# exp_4.net
KiCad netlist of a schematic drawn in EAGLE
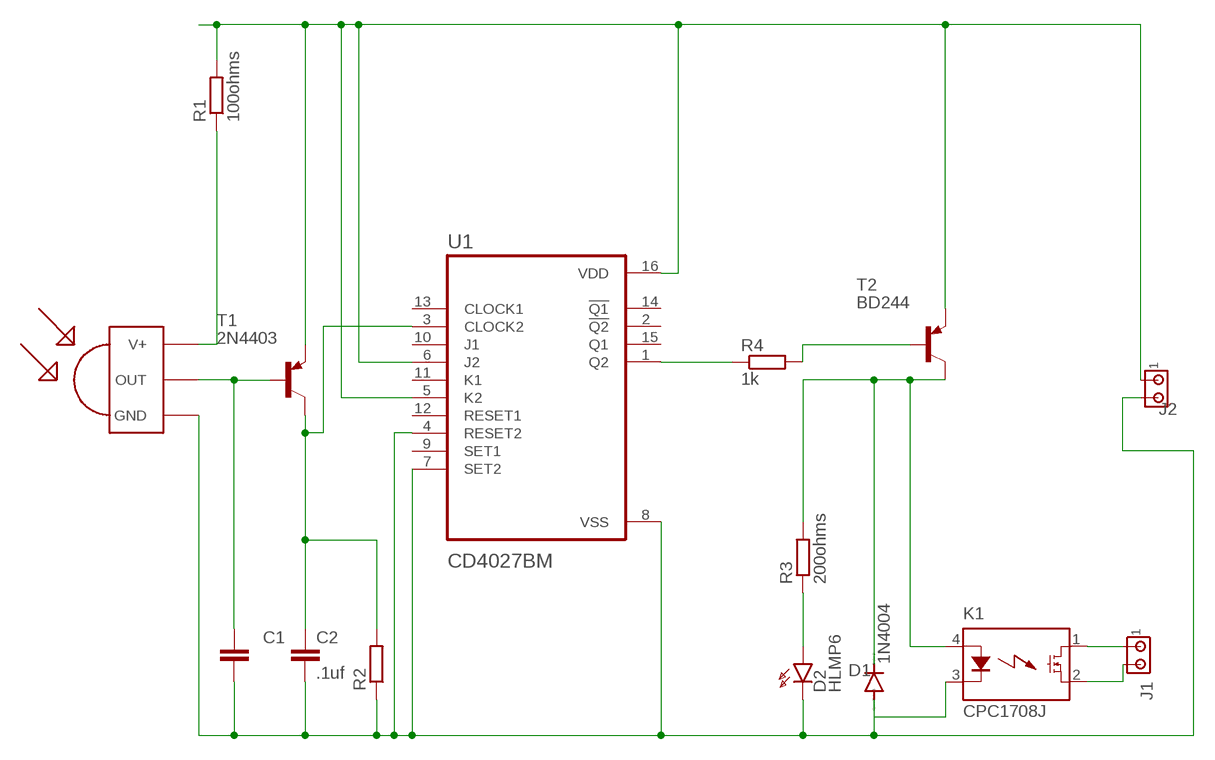
[diagram p0: schematic, sheet 1]

(export (version "E")
  (design (tool "Eeschema 10.0.6"))
  (components
    (comp (ref "C1")
      (value "C-EU025-030X050")
      (footprint "eagle-import:C025-030X050")
      (libsource (lib "eagle-import") (part "C-EU025-030X050"))
    )
    (comp (ref "C2")
      (value ".1uf")
      (footprint "eagle-import:C025-030X050")
      (libsource (lib "eagle-import") (part "C-EU025-030X050"))
    )
    (comp (ref "D1")
      (value "1N4004")
      (footprint "eagle-import:DO41-10")
      (libsource (lib "eagle-import") (part "1N4004"))
    )
    (comp (ref "D2")
      (value "HLMP6")
      (footprint "eagle-import:HLMP6")
      (fields (field (name "MF") "AGILENT TECHNOLOGIES") (field (name "MPN") "HLMP-6500"))
      (libsource (lib "eagle-import") (part "HLMP6"))
    )
    (comp (ref "J1")
      (value "MTA02-156")
      (footprint "eagle-import:1X2MTA")
      (libsource (lib "eagle-import") (part "MTA02-156"))
    )
    (comp (ref "J2")
      (value "MTA02-156")
      (footprint "eagle-import:1X2MTA")
      (libsource (lib "eagle-import") (part "MTA02-156"))
    )
    (comp (ref "K1")
      (value "CPC1708J")
      (footprint "eagle-import:I4-PAC")
      (libsource (lib "eagle-import") (part "CPC1708J"))
    )
    (comp (ref "R1")
      (value "100ohms")
      (footprint "eagle-import:0204_5")
      (libsource (lib "eagle-import") (part "R-EU_0204/5"))
    )
    (comp (ref "R2")
      (value "R-EU_0204/5")
      (footprint "eagle-import:0204_5")
      (libsource (lib "eagle-import") (part "R-EU_0204/5"))
    )
    (comp (ref "R3")
      (value "200ohms")
      (footprint "eagle-import:0204_5")
      (libsource (lib "eagle-import") (part "R-EU_0204/5"))
    )
    (comp (ref "R4")
      (value "1k")
      (footprint "eagle-import:0204_5")
      (libsource (lib "eagle-import") (part "R-EU_0204/5"))
    )
    (comp (ref "T1")
      (value "2N4403")
      (footprint "eagle-import:TO220")
      (libsource (lib "eagle-import") (part "BD244"))
    )
    (comp (ref "T2")
      (value "BD244")
      (footprint "eagle-import:TO220")
      (libsource (lib "eagle-import") (part "BD244"))
    )
    (comp (ref "U$1")
      (value "TSOP1738")
      (footprint "eagle-import:TSOP17XX")
      (fields (field (name "MF") "Vishay") (field (name "MP") "TSOP1738."))
      (libsource (lib "eagle-import") (part "TSOP1738"))
    )
    (comp (ref "U1")
      (value "CD4027BM")
      (footprint "eagle-import:SOIC127P600X175-16N")
      (fields (field (name "MF") "Texas Instruments"))
      (libsource (lib "eagle-import") (part "CD4027BM"))
    )
  )
  (nets
    (net (code "1") (name "Net-(D2-PadA)") (class "Default")
      (node (ref "D2") (pin "A") (pinfunction "A_A") (pintype "passive"))
      (node (ref "R3") (pin "1") (pinfunction "1_1") (pintype "passive"))
    )
    (net (code "2") (name "Net-(K1-A)") (class "Default")
      (node (ref "D1") (pin "C") (pinfunction "C_C") (pintype "passive"))
      (node (ref "K1") (pin "4") (pinfunction "A_4") (pintype "passive"))
      (node (ref "R3") (pin "2") (pinfunction "2_2") (pintype "passive"))
      (node (ref "T2") (pin "2") (pinfunction "C_2") (pintype "passive"))
    )
    (net (code "3") (name "Net-(K1-DS1)") (class "Default")
      (node (ref "J1") (pin "1") (pinfunction "1_1") (pintype "passive"))
      (node (ref "K1") (pin "1") (pinfunction "DS1_1") (pintype "passive"))
    )
    (net (code "4") (name "Net-(K1-DS2)") (class "Default")
      (node (ref "J1") (pin "2") (pinfunction "2_2") (pintype "passive"))
      (node (ref "K1") (pin "2") (pinfunction "DS2_2") (pintype "passive"))
    )
    (net (code "5") (name "Net-(K1-K)") (class "Default")
      (node (ref "C1") (pin "2") (pinfunction "2_2") (pintype "passive"))
      (node (ref "C2") (pin "2") (pinfunction "2_2") (pintype "passive"))
      (node (ref "D1") (pin "A") (pinfunction "A_A") (pintype "passive"))
      (node (ref "D2") (pin "K") (pinfunction "K_K") (pintype "passive"))
      (node (ref "J2") (pin "2") (pinfunction "2_2") (pintype "passive"))
      (node (ref "K1") (pin "3") (pinfunction "K_3") (pintype "passive"))
      (node (ref "R2") (pin "1") (pinfunction "1_1") (pintype "passive"))
      (node (ref "U$1") (pin "GND") (pinfunction "GND_GND") (pintype "bidirectional"))
      (node (ref "U1") (pin "4") (pinfunction "RESET2_4") (pintype "input"))
      (node (ref "U1") (pin "7") (pinfunction "SET2_7") (pintype "input"))
      (node (ref "U1") (pin "8") (pinfunction "VSS_8") (pintype "power_in"))
    )
    (net (code "6") (name "Net-(R1-Pad1)") (class "Default")
      (node (ref "R1") (pin "1") (pinfunction "1_1") (pintype "passive"))
      (node (ref "U$1") (pin "V+") (pinfunction "V+_V+") (pintype "bidirectional"))
    )
    (net (code "7") (name "Net-(T1-B)") (class "Default")
      (node (ref "C1") (pin "1") (pinfunction "1_1") (pintype "passive"))
      (node (ref "T1") (pin "1") (pinfunction "B_1") (pintype "passive"))
      (node (ref "U$1") (pin "OUT") (pinfunction "OUT_OUT") (pintype "bidirectional"))
    )
    (net (code "8") (name "Net-(T1-C)") (class "Default")
      (node (ref "C2") (pin "1") (pinfunction "1_1") (pintype "passive"))
      (node (ref "R2") (pin "2") (pinfunction "2_2") (pintype "passive"))
      (node (ref "T1") (pin "2") (pinfunction "C_2") (pintype "passive"))
      (node (ref "U1") (pin "3") (pinfunction "CLOCK2_3") (pintype "input"))
    )
    (net (code "9") (name "Net-(T1-E)") (class "Default")
      (node (ref "J2") (pin "1") (pinfunction "1_1") (pintype "passive"))
      (node (ref "R1") (pin "2") (pinfunction "2_2") (pintype "passive"))
      (node (ref "T1") (pin "3") (pinfunction "E_3") (pintype "passive"))
      (node (ref "T2") (pin "3") (pinfunction "E_3") (pintype "passive"))
      (node (ref "U1") (pin "16") (pinfunction "VDD_16") (pintype "power_in"))
      (node (ref "U1") (pin "5") (pinfunction "K2_5") (pintype "input"))
      (node (ref "U1") (pin "6") (pinfunction "J2_6") (pintype "input"))
    )
    (net (code "10") (name "Net-(T2-B)") (class "Default")
      (node (ref "R4") (pin "2") (pinfunction "2_2") (pintype "passive"))
      (node (ref "T2") (pin "1") (pinfunction "B_1") (pintype "passive"))
    )
    (net (code "11") (name "Net-(U1-Q2)") (class "Default")
      (node (ref "R4") (pin "1") (pinfunction "1_1") (pintype "passive"))
      (node (ref "U1") (pin "1") (pinfunction "Q2_1") (pintype "output"))
    )
    (net (code "12") (name "unconnected-(U1-CLOCK1-Pad13)") (class "Default")
      (node (ref "U1") (pin "13") (pinfunction "CLOCK1_13") (pintype "input"))
    )
    (net (code "13") (name "unconnected-(U1-J1-Pad10)") (class "Default")
      (node (ref "U1") (pin "10") (pinfunction "J1_10") (pintype "input"))
    )
    (net (code "14") (name "unconnected-(U1-K1-Pad11)") (class "Default")
      (node (ref "U1") (pin "11") (pinfunction "K1_11") (pintype "input"))
    )
    (net (code "15") (name "unconnected-(U1-Q1-Pad15)") (class "Default")
      (node (ref "U1") (pin "15") (pinfunction "Q1_15") (pintype "output"))
    )
    (net (code "16") (name "unconnected-(U1-RESET1-Pad12)") (class "Default")
      (node (ref "U1") (pin "12") (pinfunction "RESET1_12") (pintype "input"))
    )
    (net (code "17") (name "unconnected-(U1-SET1-Pad9)") (class "Default")
      (node (ref "U1") (pin "9") (pinfunction "SET1_9") (pintype "input"))
    )
    (net (code "18") (name "unconnected-(U1-~{Q1}-Pad14)") (class "Default")
      (node (ref "U1") (pin "14") (pinfunction "~{Q1}_14") (pintype "output"))
    )
    (net (code "19") (name "unconnected-(U1-~{Q2}-Pad2)") (class "Default")
      (node (ref "U1") (pin "2") (pinfunction "~{Q2}_2") (pintype "output"))
    )
  )
)
